# led_and_buttons.net
KiCad netlist of a schematic drawn in Altium Designer
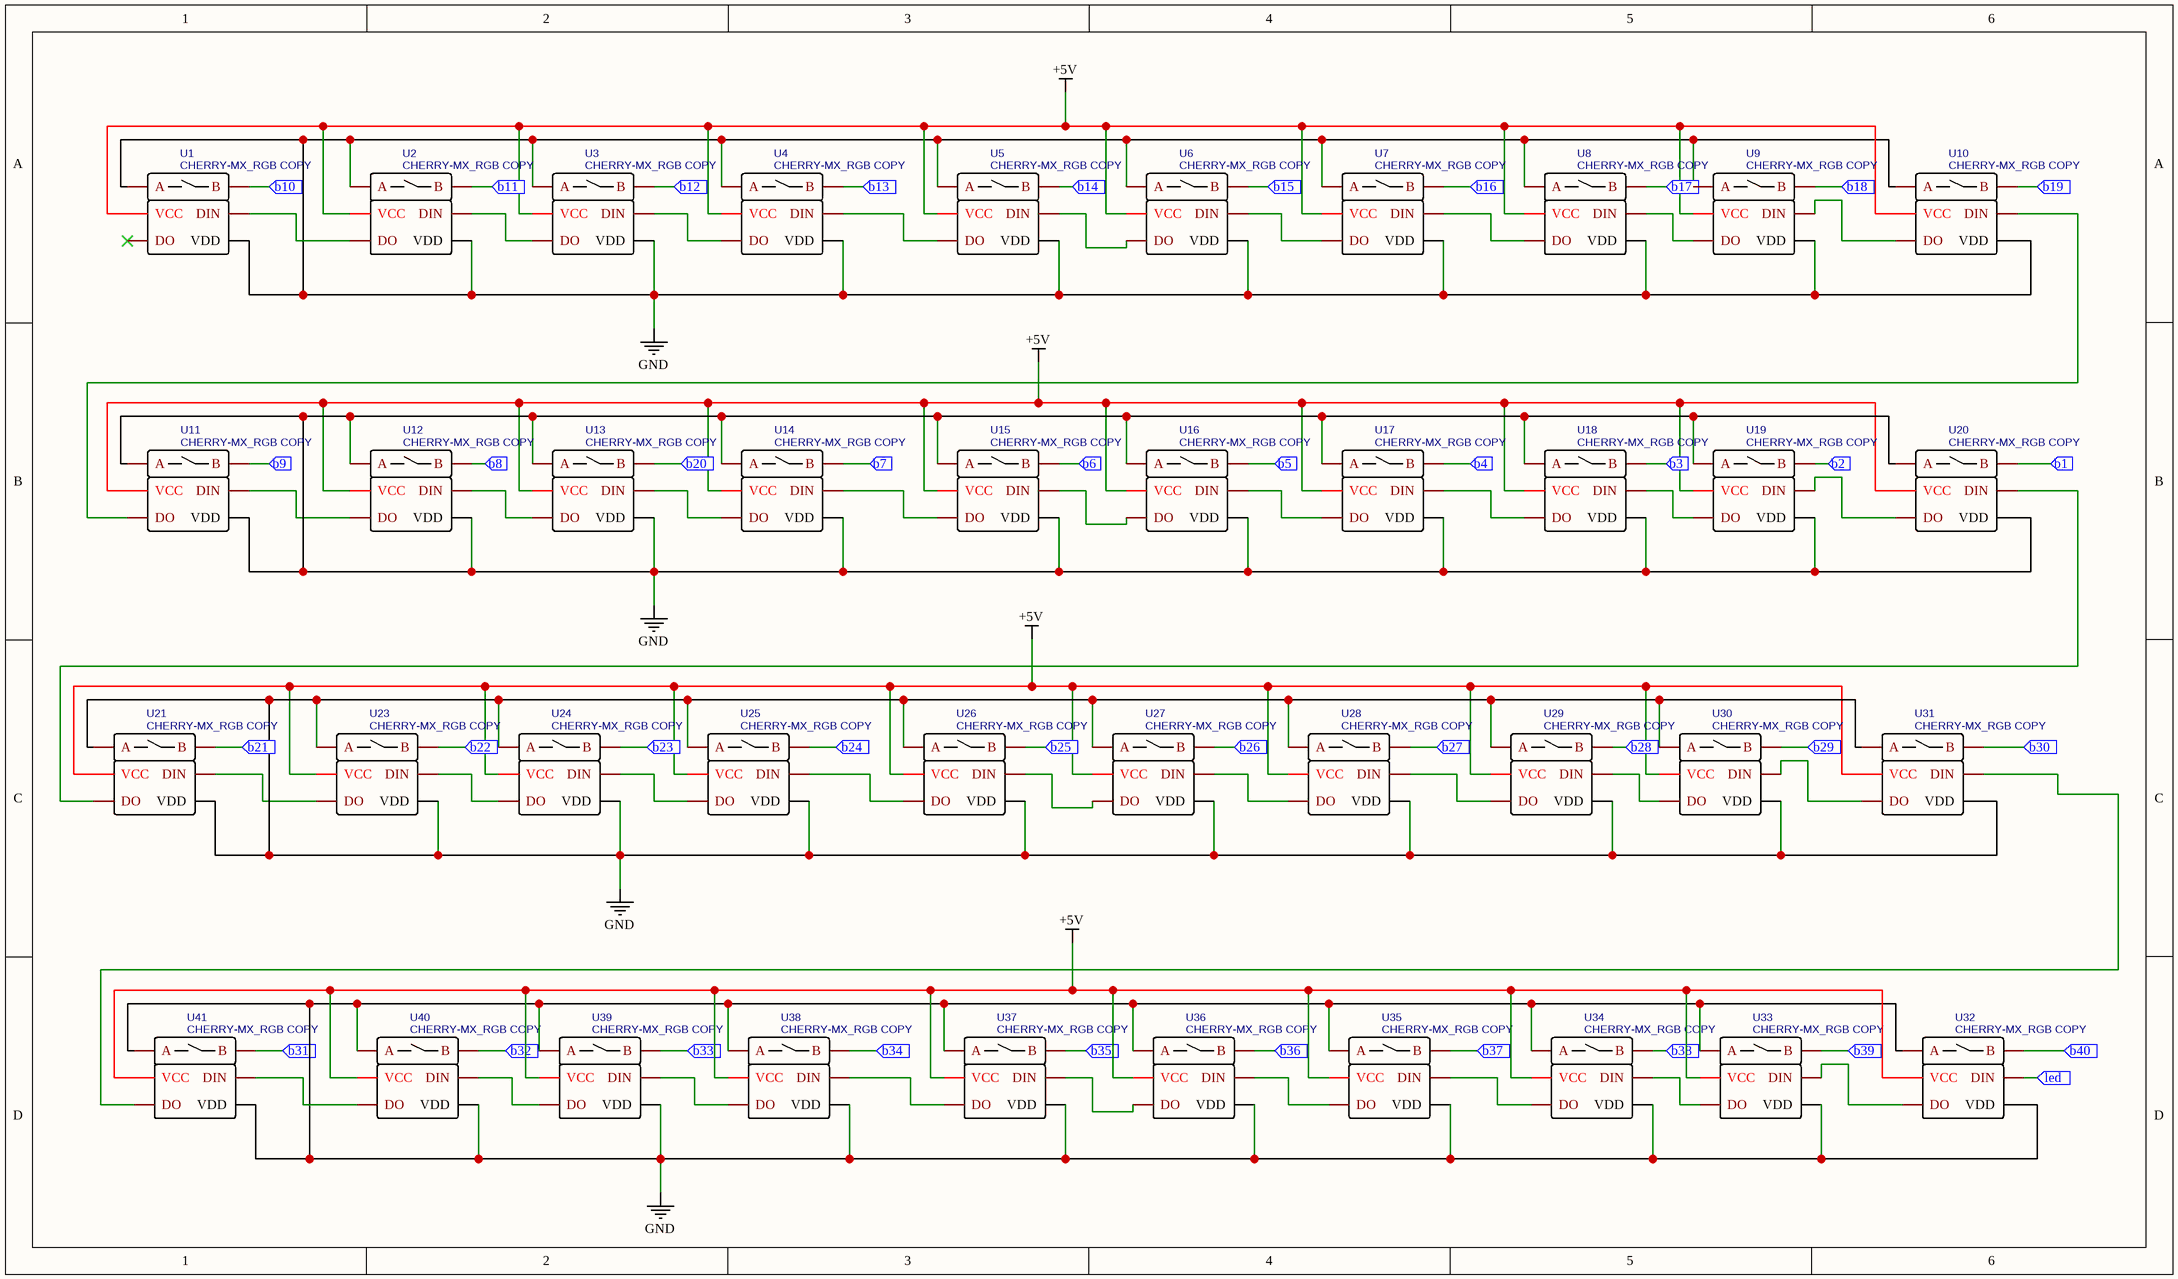
[diagram p0: led and buttons.schdoc]

(export (version "E")
  (design (tool "Eeschema 10.0.6"))
  (components
    (comp (ref "U1")
      (value "CHERRY-MX_RGB COPY")
      (fields (field (name "CONTRIBUTOR") "unrealin01"))
      (libsource (lib "altium-import") (part "root_0_CHERRY-MX_RGB COPY_"))
    )
    (comp (ref "U2")
      (value "CHERRY-MX_RGB COPY")
      (fields (field (name "CONTRIBUTOR") "unrealin01"))
      (libsource (lib "altium-import") (part "root_0_CHERRY-MX_RGB COPY_"))
    )
    (comp (ref "U3")
      (value "CHERRY-MX_RGB COPY")
      (fields (field (name "CONTRIBUTOR") "unrealin01"))
      (libsource (lib "altium-import") (part "root_0_CHERRY-MX_RGB COPY_"))
    )
    (comp (ref "U4")
      (value "CHERRY-MX_RGB COPY")
      (fields (field (name "CONTRIBUTOR") "unrealin01"))
      (libsource (lib "altium-import") (part "root_0_CHERRY-MX_RGB COPY_"))
    )
    (comp (ref "U5")
      (value "CHERRY-MX_RGB COPY")
      (fields (field (name "CONTRIBUTOR") "unrealin01"))
      (libsource (lib "altium-import") (part "root_0_CHERRY-MX_RGB COPY_"))
    )
    (comp (ref "U6")
      (value "CHERRY-MX_RGB COPY")
      (fields (field (name "CONTRIBUTOR") "unrealin01"))
      (libsource (lib "altium-import") (part "root_0_CHERRY-MX_RGB COPY_"))
    )
    (comp (ref "U7")
      (value "CHERRY-MX_RGB COPY")
      (fields (field (name "CONTRIBUTOR") "unrealin01"))
      (libsource (lib "altium-import") (part "root_0_CHERRY-MX_RGB COPY_"))
    )
    (comp (ref "U8")
      (value "CHERRY-MX_RGB COPY")
      (fields (field (name "CONTRIBUTOR") "unrealin01"))
      (libsource (lib "altium-import") (part "root_0_CHERRY-MX_RGB COPY_"))
    )
    (comp (ref "U9")
      (value "CHERRY-MX_RGB COPY")
      (fields (field (name "CONTRIBUTOR") "unrealin01"))
      (libsource (lib "altium-import") (part "root_0_CHERRY-MX_RGB COPY_"))
    )
    (comp (ref "U10")
      (value "CHERRY-MX_RGB COPY")
      (fields (field (name "CONTRIBUTOR") "unrealin01"))
      (libsource (lib "altium-import") (part "root_0_CHERRY-MX_RGB COPY_"))
    )
    (comp (ref "U11")
      (value "CHERRY-MX_RGB COPY")
      (fields (field (name "CONTRIBUTOR") "unrealin01"))
      (libsource (lib "altium-import") (part "root_0_CHERRY-MX_RGB COPY_"))
    )
    (comp (ref "U12")
      (value "CHERRY-MX_RGB COPY")
      (fields (field (name "CONTRIBUTOR") "unrealin01"))
      (libsource (lib "altium-import") (part "root_0_CHERRY-MX_RGB COPY_"))
    )
    (comp (ref "U13")
      (value "CHERRY-MX_RGB COPY")
      (fields (field (name "CONTRIBUTOR") "unrealin01"))
      (libsource (lib "altium-import") (part "root_0_CHERRY-MX_RGB COPY_"))
    )
    (comp (ref "U14")
      (value "CHERRY-MX_RGB COPY")
      (fields (field (name "CONTRIBUTOR") "unrealin01"))
      (libsource (lib "altium-import") (part "root_0_CHERRY-MX_RGB COPY_"))
    )
    (comp (ref "U15")
      (value "CHERRY-MX_RGB COPY")
      (fields (field (name "CONTRIBUTOR") "unrealin01"))
      (libsource (lib "altium-import") (part "root_0_CHERRY-MX_RGB COPY_"))
    )
    (comp (ref "U16")
      (value "CHERRY-MX_RGB COPY")
      (fields (field (name "CONTRIBUTOR") "unrealin01"))
      (libsource (lib "altium-import") (part "root_0_CHERRY-MX_RGB COPY_"))
    )
    (comp (ref "U17")
      (value "CHERRY-MX_RGB COPY")
      (fields (field (name "CONTRIBUTOR") "unrealin01"))
      (libsource (lib "altium-import") (part "root_0_CHERRY-MX_RGB COPY_"))
    )
    (comp (ref "U18")
      (value "CHERRY-MX_RGB COPY")
      (fields (field (name "CONTRIBUTOR") "unrealin01"))
      (libsource (lib "altium-import") (part "root_0_CHERRY-MX_RGB COPY_"))
    )
    (comp (ref "U19")
      (value "CHERRY-MX_RGB COPY")
      (fields (field (name "CONTRIBUTOR") "unrealin01"))
      (libsource (lib "altium-import") (part "root_0_CHERRY-MX_RGB COPY_"))
    )
    (comp (ref "U20")
      (value "CHERRY-MX_RGB COPY")
      (fields (field (name "CONTRIBUTOR") "unrealin01"))
      (libsource (lib "altium-import") (part "root_0_CHERRY-MX_RGB COPY_"))
    )
    (comp (ref "U21")
      (value "CHERRY-MX_RGB COPY")
      (fields (field (name "CONTRIBUTOR") "unrealin01"))
      (libsource (lib "altium-import") (part "root_0_CHERRY-MX_RGB COPY_"))
    )
    (comp (ref "U23")
      (value "CHERRY-MX_RGB COPY")
      (fields (field (name "CONTRIBUTOR") "unrealin01"))
      (libsource (lib "altium-import") (part "root_0_CHERRY-MX_RGB COPY_"))
    )
    (comp (ref "U24")
      (value "CHERRY-MX_RGB COPY")
      (fields (field (name "CONTRIBUTOR") "unrealin01"))
      (libsource (lib "altium-import") (part "root_0_CHERRY-MX_RGB COPY_"))
    )
    (comp (ref "U25")
      (value "CHERRY-MX_RGB COPY")
      (fields (field (name "CONTRIBUTOR") "unrealin01"))
      (libsource (lib "altium-import") (part "root_0_CHERRY-MX_RGB COPY_"))
    )
    (comp (ref "U26")
      (value "CHERRY-MX_RGB COPY")
      (fields (field (name "CONTRIBUTOR") "unrealin01"))
      (libsource (lib "altium-import") (part "root_0_CHERRY-MX_RGB COPY_"))
    )
    (comp (ref "U27")
      (value "CHERRY-MX_RGB COPY")
      (fields (field (name "CONTRIBUTOR") "unrealin01"))
      (libsource (lib "altium-import") (part "root_0_CHERRY-MX_RGB COPY_"))
    )
    (comp (ref "U28")
      (value "CHERRY-MX_RGB COPY")
      (fields (field (name "CONTRIBUTOR") "unrealin01"))
      (libsource (lib "altium-import") (part "root_0_CHERRY-MX_RGB COPY_"))
    )
    (comp (ref "U29")
      (value "CHERRY-MX_RGB COPY")
      (fields (field (name "CONTRIBUTOR") "unrealin01"))
      (libsource (lib "altium-import") (part "root_0_CHERRY-MX_RGB COPY_"))
    )
    (comp (ref "U30")
      (value "CHERRY-MX_RGB COPY")
      (fields (field (name "CONTRIBUTOR") "unrealin01"))
      (libsource (lib "altium-import") (part "root_0_CHERRY-MX_RGB COPY_"))
    )
    (comp (ref "U31")
      (value "CHERRY-MX_RGB COPY")
      (fields (field (name "CONTRIBUTOR") "unrealin01"))
      (libsource (lib "altium-import") (part "root_0_CHERRY-MX_RGB COPY_"))
    )
    (comp (ref "U32")
      (value "CHERRY-MX_RGB COPY")
      (fields (field (name "CONTRIBUTOR") "unrealin01"))
      (libsource (lib "altium-import") (part "root_0_CHERRY-MX_RGB COPY_"))
    )
    (comp (ref "U33")
      (value "CHERRY-MX_RGB COPY")
      (fields (field (name "CONTRIBUTOR") "unrealin01"))
      (libsource (lib "altium-import") (part "root_0_CHERRY-MX_RGB COPY_"))
    )
    (comp (ref "U34")
      (value "CHERRY-MX_RGB COPY")
      (fields (field (name "CONTRIBUTOR") "unrealin01"))
      (libsource (lib "altium-import") (part "root_0_CHERRY-MX_RGB COPY_"))
    )
    (comp (ref "U35")
      (value "CHERRY-MX_RGB COPY")
      (fields (field (name "CONTRIBUTOR") "unrealin01"))
      (libsource (lib "altium-import") (part "root_0_CHERRY-MX_RGB COPY_"))
    )
    (comp (ref "U36")
      (value "CHERRY-MX_RGB COPY")
      (fields (field (name "CONTRIBUTOR") "unrealin01"))
      (libsource (lib "altium-import") (part "root_0_CHERRY-MX_RGB COPY_"))
    )
    (comp (ref "U37")
      (value "CHERRY-MX_RGB COPY")
      (fields (field (name "CONTRIBUTOR") "unrealin01"))
      (libsource (lib "altium-import") (part "root_0_CHERRY-MX_RGB COPY_"))
    )
    (comp (ref "U38")
      (value "CHERRY-MX_RGB COPY")
      (fields (field (name "CONTRIBUTOR") "unrealin01"))
      (libsource (lib "altium-import") (part "root_0_CHERRY-MX_RGB COPY_"))
    )
    (comp (ref "U39")
      (value "CHERRY-MX_RGB COPY")
      (fields (field (name "CONTRIBUTOR") "unrealin01"))
      (libsource (lib "altium-import") (part "root_0_CHERRY-MX_RGB COPY_"))
    )
    (comp (ref "U40")
      (value "CHERRY-MX_RGB COPY")
      (fields (field (name "CONTRIBUTOR") "unrealin01"))
      (libsource (lib "altium-import") (part "root_0_CHERRY-MX_RGB COPY_"))
    )
    (comp (ref "U41")
      (value "CHERRY-MX_RGB COPY")
      (fields (field (name "CONTRIBUTOR") "unrealin01"))
      (libsource (lib "altium-import") (part "root_0_CHERRY-MX_RGB COPY_"))
    )
  )
  (nets
    (net (code "1") (name "+5V") (class "Default")
      (node (ref "U1") (pin "3") (pinfunction "VCC_3") (pintype "passive"))
      (node (ref "U10") (pin "3") (pinfunction "VCC_3") (pintype "passive"))
      (node (ref "U11") (pin "3") (pinfunction "VCC_3") (pintype "passive"))
      (node (ref "U12") (pin "3") (pinfunction "VCC_3") (pintype "passive"))
      (node (ref "U13") (pin "3") (pinfunction "VCC_3") (pintype "passive"))
      (node (ref "U14") (pin "3") (pinfunction "VCC_3") (pintype "passive"))
      (node (ref "U15") (pin "3") (pinfunction "VCC_3") (pintype "passive"))
      (node (ref "U16") (pin "3") (pinfunction "VCC_3") (pintype "passive"))
      (node (ref "U17") (pin "3") (pinfunction "VCC_3") (pintype "passive"))
      (node (ref "U18") (pin "3") (pinfunction "VCC_3") (pintype "passive"))
      (node (ref "U19") (pin "3") (pinfunction "VCC_3") (pintype "passive"))
      (node (ref "U2") (pin "3") (pinfunction "VCC_3") (pintype "passive"))
      (node (ref "U20") (pin "3") (pinfunction "VCC_3") (pintype "passive"))
      (node (ref "U21") (pin "3") (pinfunction "VCC_3") (pintype "passive"))
      (node (ref "U23") (pin "3") (pinfunction "VCC_3") (pintype "passive"))
      (node (ref "U24") (pin "3") (pinfunction "VCC_3") (pintype "passive"))
      (node (ref "U25") (pin "3") (pinfunction "VCC_3") (pintype "passive"))
      (node (ref "U26") (pin "3") (pinfunction "VCC_3") (pintype "passive"))
      (node (ref "U27") (pin "3") (pinfunction "VCC_3") (pintype "passive"))
      (node (ref "U28") (pin "3") (pinfunction "VCC_3") (pintype "passive"))
      (node (ref "U29") (pin "3") (pinfunction "VCC_3") (pintype "passive"))
      (node (ref "U3") (pin "3") (pinfunction "VCC_3") (pintype "passive"))
      (node (ref "U30") (pin "3") (pinfunction "VCC_3") (pintype "passive"))
      (node (ref "U31") (pin "3") (pinfunction "VCC_3") (pintype "passive"))
      (node (ref "U32") (pin "3") (pinfunction "VCC_3") (pintype "passive"))
      (node (ref "U33") (pin "3") (pinfunction "VCC_3") (pintype "passive"))
      (node (ref "U34") (pin "3") (pinfunction "VCC_3") (pintype "passive"))
      (node (ref "U35") (pin "3") (pinfunction "VCC_3") (pintype "passive"))
      (node (ref "U36") (pin "3") (pinfunction "VCC_3") (pintype "passive"))
      (node (ref "U37") (pin "3") (pinfunction "VCC_3") (pintype "passive"))
      (node (ref "U38") (pin "3") (pinfunction "VCC_3") (pintype "passive"))
      (node (ref "U39") (pin "3") (pinfunction "VCC_3") (pintype "passive"))
      (node (ref "U4") (pin "3") (pinfunction "VCC_3") (pintype "passive"))
      (node (ref "U40") (pin "3") (pinfunction "VCC_3") (pintype "passive"))
      (node (ref "U41") (pin "3") (pinfunction "VCC_3") (pintype "passive"))
      (node (ref "U5") (pin "3") (pinfunction "VCC_3") (pintype "passive"))
      (node (ref "U6") (pin "3") (pinfunction "VCC_3") (pintype "passive"))
      (node (ref "U7") (pin "3") (pinfunction "VCC_3") (pintype "passive"))
      (node (ref "U8") (pin "3") (pinfunction "VCC_3") (pintype "passive"))
      (node (ref "U9") (pin "3") (pinfunction "VCC_3") (pintype "passive"))
    )
    (net (code "2") (name "/b1") (class "Default")
      (node (ref "U20") (pin "2") (pinfunction "B_2") (pintype "passive"))
    )
    (net (code "3") (name "/b2") (class "Default")
      (node (ref "U19") (pin "2") (pinfunction "B_2") (pintype "passive"))
    )
    (net (code "4") (name "/b3") (class "Default")
      (node (ref "U18") (pin "2") (pinfunction "B_2") (pintype "passive"))
    )
    (net (code "5") (name "/b4") (class "Default")
      (node (ref "U17") (pin "2") (pinfunction "B_2") (pintype "passive"))
    )
    (net (code "6") (name "/b5") (class "Default")
      (node (ref "U16") (pin "2") (pinfunction "B_2") (pintype "passive"))
    )
    (net (code "7") (name "/b6") (class "Default")
      (node (ref "U15") (pin "2") (pinfunction "B_2") (pintype "passive"))
    )
    (net (code "8") (name "/b7") (class "Default")
      (node (ref "U14") (pin "2") (pinfunction "B_2") (pintype "passive"))
    )
    (net (code "9") (name "/b8") (class "Default")
      (node (ref "U12") (pin "2") (pinfunction "B_2") (pintype "passive"))
    )
    (net (code "10") (name "/b9") (class "Default")
      (node (ref "U11") (pin "2") (pinfunction "B_2") (pintype "passive"))
    )
    (net (code "11") (name "/b10") (class "Default")
      (node (ref "U1") (pin "2") (pinfunction "B_2") (pintype "passive"))
    )
    (net (code "12") (name "/b11") (class "Default")
      (node (ref "U2") (pin "2") (pinfunction "B_2") (pintype "passive"))
    )
    (net (code "13") (name "/b12") (class "Default")
      (node (ref "U3") (pin "2") (pinfunction "B_2") (pintype "passive"))
    )
    (net (code "14") (name "/b13") (class "Default")
      (node (ref "U4") (pin "2") (pinfunction "B_2") (pintype "passive"))
    )
    (net (code "15") (name "/b14") (class "Default")
      (node (ref "U5") (pin "2") (pinfunction "B_2") (pintype "passive"))
    )
    (net (code "16") (name "/b15") (class "Default")
      (node (ref "U6") (pin "2") (pinfunction "B_2") (pintype "passive"))
    )
    (net (code "17") (name "/b16") (class "Default")
      (node (ref "U7") (pin "2") (pinfunction "B_2") (pintype "passive"))
    )
    (net (code "18") (name "/b17") (class "Default")
      (node (ref "U8") (pin "2") (pinfunction "B_2") (pintype "passive"))
    )
    (net (code "19") (name "/b18") (class "Default")
      (node (ref "U9") (pin "2") (pinfunction "B_2") (pintype "passive"))
    )
    (net (code "20") (name "/b19") (class "Default")
      (node (ref "U10") (pin "2") (pinfunction "B_2") (pintype "passive"))
    )
    (net (code "21") (name "/b20") (class "Default")
      (node (ref "U13") (pin "2") (pinfunction "B_2") (pintype "passive"))
    )
    (net (code "22") (name "/b21") (class "Default")
      (node (ref "U21") (pin "2") (pinfunction "B_2") (pintype "passive"))
    )
    (net (code "23") (name "/b22") (class "Default")
      (node (ref "U23") (pin "2") (pinfunction "B_2") (pintype "passive"))
    )
    (net (code "24") (name "/b23") (class "Default")
      (node (ref "U24") (pin "2") (pinfunction "B_2") (pintype "passive"))
    )
    (net (code "25") (name "/b24") (class "Default")
      (node (ref "U25") (pin "2") (pinfunction "B_2") (pintype "passive"))
    )
    (net (code "26") (name "/b25") (class "Default")
      (node (ref "U26") (pin "2") (pinfunction "B_2") (pintype "passive"))
    )
    (net (code "27") (name "/b26") (class "Default")
      (node (ref "U27") (pin "2") (pinfunction "B_2") (pintype "passive"))
    )
    (net (code "28") (name "/b27") (class "Default")
      (node (ref "U28") (pin "2") (pinfunction "B_2") (pintype "passive"))
    )
    (net (code "29") (name "/b28") (class "Default")
      (node (ref "U29") (pin "2") (pinfunction "B_2") (pintype "passive"))
    )
    (net (code "30") (name "/b29") (class "Default")
      (node (ref "U30") (pin "2") (pinfunction "B_2") (pintype "passive"))
    )
    (net (code "31") (name "/b30") (class "Default")
      (node (ref "U31") (pin "2") (pinfunction "B_2") (pintype "passive"))
    )
    (net (code "32") (name "/b31") (class "Default")
      (node (ref "U41") (pin "2") (pinfunction "B_2") (pintype "passive"))
    )
    (net (code "33") (name "/b32") (class "Default")
      (node (ref "U40") (pin "2") (pinfunction "B_2") (pintype "passive"))
    )
    (net (code "34") (name "/b33") (class "Default")
      (node (ref "U39") (pin "2") (pinfunction "B_2") (pintype "passive"))
    )
    (net (code "35") (name "/b34") (class "Default")
      (node (ref "U38") (pin "2") (pinfunction "B_2") (pintype "passive"))
    )
    (net (code "36") (name "/b35") (class "Default")
      (node (ref "U37") (pin "2") (pinfunction "B_2") (pintype "passive"))
    )
    (net (code "37") (name "/b36") (class "Default")
      (node (ref "U36") (pin "2") (pinfunction "B_2") (pintype "passive"))
    )
    (net (code "38") (name "/b37") (class "Default")
      (node (ref "U35") (pin "2") (pinfunction "B_2") (pintype "passive"))
    )
    (net (code "39") (name "/b38") (class "Default")
      (node (ref "U34") (pin "2") (pinfunction "B_2") (pintype "passive"))
    )
    (net (code "40") (name "/b39") (class "Default")
      (node (ref "U33") (pin "2") (pinfunction "B_2") (pintype "passive"))
    )
    (net (code "41") (name "/b40") (class "Default")
      (node (ref "U32") (pin "2") (pinfunction "B_2") (pintype "passive"))
    )
    (net (code "42") (name "/led") (class "Default")
      (node (ref "U32") (pin "6") (pinfunction "DIN_6") (pintype "passive"))
    )
    (net (code "43") (name "GND") (class "Default")
      (node (ref "U1") (pin "1") (pinfunction "A_1") (pintype "passive"))
      (node (ref "U1") (pin "5") (pinfunction "VDD_5") (pintype "passive"))
      (node (ref "U10") (pin "1") (pinfunction "A_1") (pintype "passive"))
      (node (ref "U10") (pin "5") (pinfunction "VDD_5") (pintype "passive"))
      (node (ref "U11") (pin "1") (pinfunction "A_1") (pintype "passive"))
      (node (ref "U11") (pin "5") (pinfunction "VDD_5") (pintype "passive"))
      (node (ref "U12") (pin "1") (pinfunction "A_1") (pintype "passive"))
      (node (ref "U12") (pin "5") (pinfunction "VDD_5") (pintype "passive"))
      (node (ref "U13") (pin "1") (pinfunction "A_1") (pintype "passive"))
      (node (ref "U13") (pin "5") (pinfunction "VDD_5") (pintype "passive"))
      (node (ref "U14") (pin "1") (pinfunction "A_1") (pintype "passive"))
      (node (ref "U14") (pin "5") (pinfunction "VDD_5") (pintype "passive"))
      (node (ref "U15") (pin "1") (pinfunction "A_1") (pintype "passive"))
      (node (ref "U15") (pin "5") (pinfunction "VDD_5") (pintype "passive"))
      (node (ref "U16") (pin "1") (pinfunction "A_1") (pintype "passive"))
      (node (ref "U16") (pin "5") (pinfunction "VDD_5") (pintype "passive"))
      (node (ref "U17") (pin "1") (pinfunction "A_1") (pintype "passive"))
      (node (ref "U17") (pin "5") (pinfunction "VDD_5") (pintype "passive"))
      (node (ref "U18") (pin "1") (pinfunction "A_1") (pintype "passive"))
      (node (ref "U18") (pin "5") (pinfunction "VDD_5") (pintype "passive"))
      (node (ref "U19") (pin "1") (pinfunction "A_1") (pintype "passive"))
      (node (ref "U19") (pin "5") (pinfunction "VDD_5") (pintype "passive"))
      (node (ref "U2") (pin "1") (pinfunction "A_1") (pintype "passive"))
      (node (ref "U2") (pin "5") (pinfunction "VDD_5") (pintype "passive"))
      (node (ref "U20") (pin "1") (pinfunction "A_1") (pintype "passive"))
      (node (ref "U20") (pin "5") (pinfunction "VDD_5") (pintype "passive"))
      (node (ref "U21") (pin "1") (pinfunction "A_1") (pintype "passive"))
      (node (ref "U21") (pin "5") (pinfunction "VDD_5") (pintype "passive"))
      (node (ref "U23") (pin "1") (pinfunction "A_1") (pintype "passive"))
      (node (ref "U23") (pin "5") (pinfunction "VDD_5") (pintype "passive"))
      (node (ref "U24") (pin "1") (pinfunction "A_1") (pintype "passive"))
      (node (ref "U24") (pin "5") (pinfunction "VDD_5") (pintype "passive"))
      (node (ref "U25") (pin "1") (pinfunction "A_1") (pintype "passive"))
      (node (ref "U25") (pin "5") (pinfunction "VDD_5") (pintype "passive"))
      (node (ref "U26") (pin "1") (pinfunction "A_1") (pintype "passive"))
      (node (ref "U26") (pin "5") (pinfunction "VDD_5") (pintype "passive"))
      (node (ref "U27") (pin "1") (pinfunction "A_1") (pintype "passive"))
      (node (ref "U27") (pin "5") (pinfunction "VDD_5") (pintype "passive"))
      (node (ref "U28") (pin "1") (pinfunction "A_1") (pintype "passive"))
      (node (ref "U28") (pin "5") (pinfunction "VDD_5") (pintype "passive"))
      (node (ref "U29") (pin "1") (pinfunction "A_1") (pintype "passive"))
      (node (ref "U29") (pin "5") (pinfunction "VDD_5") (pintype "passive"))
      (node (ref "U3") (pin "1") (pinfunction "A_1") (pintype "passive"))
      (node (ref "U3") (pin "5") (pinfunction "VDD_5") (pintype "passive"))
      (node (ref "U30") (pin "1") (pinfunction "A_1") (pintype "passive"))
      (node (ref "U30") (pin "5") (pinfunction "VDD_5") (pintype "passive"))
      (node (ref "U31") (pin "1") (pinfunction "A_1") (pintype "passive"))
      (node (ref "U31") (pin "5") (pinfunction "VDD_5") (pintype "passive"))
      (node (ref "U32") (pin "1") (pinfunction "A_1") (pintype "passive"))
      (node (ref "U32") (pin "5") (pinfunction "VDD_5") (pintype "passive"))
      (node (ref "U33") (pin "1") (pinfunction "A_1") (pintype "passive"))
      (node (ref "U33") (pin "5") (pinfunction "VDD_5") (pintype "passive"))
      (node (ref "U34") (pin "1") (pinfunction "A_1") (pintype "passive"))
      (node (ref "U34") (pin "5") (pinfunction "VDD_5") (pintype "passive"))
      (node (ref "U35") (pin "1") (pinfunction "A_1") (pintype "passive"))
      (node (ref "U35") (pin "5") (pinfunction "VDD_5") (pintype "passive"))
      (node (ref "U36") (pin "1") (pinfunction "A_1") (pintype "passive"))
      (node (ref "U36") (pin "5") (pinfunction "VDD_5") (pintype "passive"))
      (node (ref "U37") (pin "1") (pinfunction "A_1") (pintype "passive"))
      (node (ref "U37") (pin "5") (pinfunction "VDD_5") (pintype "passive"))
      (node (ref "U38") (pin "1") (pinfunction "A_1") (pintype "passive"))
      (node (ref "U38") (pin "5") (pinfunction "VDD_5") (pintype "passive"))
      (node (ref "U39") (pin "1") (pinfunction "A_1") (pintype "passive"))
      (node (ref "U39") (pin "5") (pinfunction "VDD_5") (pintype "passive"))
      (node (ref "U4") (pin "1") (pinfunction "A_1") (pintype "passive"))
      (node (ref "U4") (pin "5") (pinfunction "VDD_5") (pintype "passive"))
      (node (ref "U40") (pin "1") (pinfunction "A_1") (pintype "passive"))
      (node (ref "U40") (pin "5") (pinfunction "VDD_5") (pintype "passive"))
      (node (ref "U41") (pin "1") (pinfunction "A_1") (pintype "passive"))
      (node (ref "U41") (pin "5") (pinfunction "VDD_5") (pintype "passive"))
      (node (ref "U5") (pin "1") (pinfunction "A_1") (pintype "passive"))
      (node (ref "U5") (pin "5") (pinfunction "VDD_5") (pintype "passive"))
      (node (ref "U6") (pin "1") (pinfunction "A_1") (pintype "passive"))
      (node (ref "U6") (pin "5") (pinfunction "VDD_5") (pintype "passive"))
      (node (ref "U7") (pin "1") (pinfunction "A_1") (pintype "passive"))
      (node (ref "U7") (pin "5") (pinfunction "VDD_5") (pintype "passive"))
      (node (ref "U8") (pin "1") (pinfunction "A_1") (pintype "passive"))
      (node (ref "U8") (pin "5") (pinfunction "VDD_5") (pintype "passive"))
      (node (ref "U9") (pin "1") (pinfunction "A_1") (pintype "passive"))
      (node (ref "U9") (pin "5") (pinfunction "VDD_5") (pintype "passive"))
    )
    (net (code "44") (name "Net-(U1-DIN)") (class "Default")
      (node (ref "U1") (pin "6") (pinfunction "DIN_6") (pintype "passive"))
      (node (ref "U2") (pin "4") (pinfunction "DO_4") (pintype "passive"))
    )
    (net (code "45") (name "Net-(U2-DIN)") (class "Default")
      (node (ref "U2") (pin "6") (pinfunction "DIN_6") (pintype "passive"))
      (node (ref "U3") (pin "4") (pinfunction "DO_4") (pintype "passive"))
    )
    (net (code "46") (name "Net-(U3-DIN)") (class "Default")
      (node (ref "U3") (pin "6") (pinfunction "DIN_6") (pintype "passive"))
      (node (ref "U4") (pin "4") (pinfunction "DO_4") (pintype "passive"))
    )
    (net (code "47") (name "Net-(U4-DIN)") (class "Default")
      (node (ref "U4") (pin "6") (pinfunction "DIN_6") (pintype "passive"))
      (node (ref "U5") (pin "4") (pinfunction "DO_4") (pintype "passive"))
    )
    (net (code "48") (name "Net-(U5-DIN)") (class "Default")
      (node (ref "U5") (pin "6") (pinfunction "DIN_6") (pintype "passive"))
      (node (ref "U6") (pin "4") (pinfunction "DO_4") (pintype "passive"))
    )
    (net (code "49") (name "Net-(U6-DIN)") (class "Default")
      (node (ref "U6") (pin "6") (pinfunction "DIN_6") (pintype "passive"))
      (node (ref "U7") (pin "4") (pinfunction "DO_4") (pintype "passive"))
    )
    (net (code "50") (name "Net-(U7-DIN)") (class "Default")
      (node (ref "U7") (pin "6") (pinfunction "DIN_6") (pintype "passive"))
      (node (ref "U8") (pin "4") (pinfunction "DO_4") (pintype "passive"))
    )
    (net (code "51") (name "Net-(U8-DIN)") (class "Default")
      (node (ref "U8") (pin "6") (pinfunction "DIN_6") (pintype "passive"))
      (node (ref "U9") (pin "4") (pinfunction "DO_4") (pintype "passive"))
    )
    (net (code "52") (name "Net-(U10-DIN)") (class "Default")
      (node (ref "U10") (pin "6") (pinfunction "DIN_6") (pintype "passive"))
      (node (ref "U11") (pin "4") (pinfunction "DO_4") (pintype "passive"))
    )
    (net (code "53") (name "Net-(U10-DO)") (class "Default")
      (node (ref "U10") (pin "4") (pinfunction "DO_4") (pintype "passive"))
      (node (ref "U9") (pin "6") (pinfunction "DIN_6") (pintype "passive"))
    )
    (net (code "54") (name "Net-(U11-DIN)") (class "Default")
      (node (ref "U11") (pin "6") (pinfunction "DIN_6") (pintype "passive"))
      (node (ref "U12") (pin "4") (pinfunction "DO_4") (pintype "passive"))
    )
    (net (code "55") (name "Net-(U12-DIN)") (class "Default")
      (node (ref "U12") (pin "6") (pinfunction "DIN_6") (pintype "passive"))
      (node (ref "U13") (pin "4") (pinfunction "DO_4") (pintype "passive"))
    )
    (net (code "56") (name "Net-(U13-DIN)") (class "Default")
      (node (ref "U13") (pin "6") (pinfunction "DIN_6") (pintype "passive"))
      (node (ref "U14") (pin "4") (pinfunction "DO_4") (pintype "passive"))
    )
    (net (code "57") (name "Net-(U14-DIN)") (class "Default")
      (node (ref "U14") (pin "6") (pinfunction "DIN_6") (pintype "passive"))
      (node (ref "U15") (pin "4") (pinfunction "DO_4") (pintype "passive"))
    )
    (net (code "58") (name "Net-(U15-DIN)") (class "Default")
      (node (ref "U15") (pin "6") (pinfunction "DIN_6") (pintype "passive"))
      (node (ref "U16") (pin "4") (pinfunction "DO_4") (pintype "passive"))
    )
    (net (code "59") (name "Net-(U16-DIN)") (class "Default")
      (node (ref "U16") (pin "6") (pinfunction "DIN_6") (pintype "passive"))
      (node (ref "U17") (pin "4") (pinfunction "DO_4") (pintype "passive"))
    )
    (net (code "60") (name "Net-(U17-DIN)") (class "Default")
      (node (ref "U17") (pin "6") (pinfunction "DIN_6") (pintype "passive"))
      (node (ref "U18") (pin "4") (pinfunction "DO_4") (pintype "passive"))
    )
    (net (code "61") (name "Net-(U18-DIN)") (class "Default")
      (node (ref "U18") (pin "6") (pinfunction "DIN_6") (pintype "passive"))
      (node (ref "U19") (pin "4") (pinfunction "DO_4") (pintype "passive"))
    )
    (net (code "62") (name "Net-(U19-DIN)") (class "Default")
      (node (ref "U19") (pin "6") (pinfunction "DIN_6") (pintype "passive"))
      (node (ref "U20") (pin "4") (pinfunction "DO_4") (pintype "passive"))
    )
    (net (code "63") (name "Net-(U20-DIN)") (class "Default")
      (node (ref "U20") (pin "6") (pinfunction "DIN_6") (pintype "passive"))
      (node (ref "U21") (pin "4") (pinfunction "DO_4") (pintype "passive"))
    )
    (net (code "64") (name "Net-(U21-DIN)") (class "Default")
      (node (ref "U21") (pin "6") (pinfunction "DIN_6") (pintype "passive"))
      (node (ref "U23") (pin "4") (pinfunction "DO_4") (pintype "passive"))
    )
    (net (code "65") (name "Net-(U23-DIN)") (class "Default")
      (node (ref "U23") (pin "6") (pinfunction "DIN_6") (pintype "passive"))
      (node (ref "U24") (pin "4") (pinfunction "DO_4") (pintype "passive"))
    )
    (net (code "66") (name "Net-(U24-DIN)") (class "Default")
      (node (ref "U24") (pin "6") (pinfunction "DIN_6") (pintype "passive"))
      (node (ref "U25") (pin "4") (pinfunction "DO_4") (pintype "passive"))
    )
    (net (code "67") (name "Net-(U25-DIN)") (class "Default")
      (node (ref "U25") (pin "6") (pinfunction "DIN_6") (pintype "passive"))
      (node (ref "U26") (pin "4") (pinfunction "DO_4") (pintype "passive"))
    )
    (net (code "68") (name "Net-(U26-DIN)") (class "Default")
      (node (ref "U26") (pin "6") (pinfunction "DIN_6") (pintype "passive"))
      (node (ref "U27") (pin "4") (pinfunction "DO_4") (pintype "passive"))
    )
    (net (code "69") (name "Net-(U27-DIN)") (class "Default")
      (node (ref "U27") (pin "6") (pinfunction "DIN_6") (pintype "passive"))
      (node (ref "U28") (pin "4") (pinfunction "DO_4") (pintype "passive"))
    )
    (net (code "70") (name "Net-(U28-DIN)") (class "Default")
      (node (ref "U28") (pin "6") (pinfunction "DIN_6") (pintype "passive"))
      (node (ref "U29") (pin "4") (pinfunction "DO_4") (pintype "passive"))
    )
    (net (code "71") (name "Net-(U29-DIN)") (class "Default")
      (node (ref "U29") (pin "6") (pinfunction "DIN_6") (pintype "passive"))
      (node (ref "U30") (pin "4") (pinfunction "DO_4") (pintype "passive"))
    )
    (net (code "72") (name "Net-(U30-DIN)") (class "Default")
      (node (ref "U30") (pin "6") (pinfunction "DIN_6") (pintype "passive"))
      (node (ref "U31") (pin "4") (pinfunction "DO_4") (pintype "passive"))
    )
    (net (code "73") (name "Net-(U31-DIN)") (class "Default")
      (node (ref "U31") (pin "6") (pinfunction "DIN_6") (pintype "passive"))
      (node (ref "U41") (pin "4") (pinfunction "DO_4") (pintype "passive"))
    )
    (net (code "74") (name "Net-(U32-DO)") (class "Default")
      (node (ref "U32") (pin "4") (pinfunction "DO_4") (pintype "passive"))
      (node (ref "U33") (pin "6") (pinfunction "DIN_6") (pintype "passive"))
    )
    (net (code "75") (name "Net-(U33-DO)") (class "Default")
      (node (ref "U33") (pin "4") (pinfunction "DO_4") (pintype "passive"))
      (node (ref "U34") (pin "6") (pinfunction "DIN_6") (pintype "passive"))
    )
    (net (code "76") (name "Net-(U34-DO)") (class "Default")
      (node (ref "U34") (pin "4") (pinfunction "DO_4") (pintype "passive"))
      (node (ref "U35") (pin "6") (pinfunction "DIN_6") (pintype "passive"))
    )
    (net (code "77") (name "Net-(U35-DO)") (class "Default")
      (node (ref "U35") (pin "4") (pinfunction "DO_4") (pintype "passive"))
      (node (ref "U36") (pin "6") (pinfunction "DIN_6") (pintype "passive"))
    )
    (net (code "78") (name "Net-(U36-DO)") (class "Default")
      (node (ref "U36") (pin "4") (pinfunction "DO_4") (pintype "passive"))
      (node (ref "U37") (pin "6") (pinfunction "DIN_6") (pintype "passive"))
    )
    (net (code "79") (name "Net-(U37-DO)") (class "Default")
      (node (ref "U37") (pin "4") (pinfunction "DO_4") (pintype "passive"))
      (node (ref "U38") (pin "6") (pinfunction "DIN_6") (pintype "passive"))
    )
    (net (code "80") (name "Net-(U38-DO)") (class "Default")
      (node (ref "U38") (pin "4") (pinfunction "DO_4") (pintype "passive"))
      (node (ref "U39") (pin "6") (pinfunction "DIN_6") (pintype "passive"))
    )
    (net (code "81") (name "Net-(U39-DO)") (class "Default")
      (node (ref "U39") (pin "4") (pinfunction "DO_4") (pintype "passive"))
      (node (ref "U40") (pin "6") (pinfunction "DIN_6") (pintype "passive"))
    )
    (net (code "82") (name "Net-(U40-DO)") (class "Default")
      (node (ref "U40") (pin "4") (pinfunction "DO_4") (pintype "passive"))
      (node (ref "U41") (pin "6") (pinfunction "DIN_6") (pintype "passive"))
    )
    (net (code "83") (name "unconnected-(U1-DO-Pad4)") (class "Default")
      (node (ref "U1") (pin "4") (pinfunction "DO_4") (pintype "passive+no_connect"))
    )
  )
)
